# Board2.net
KiCad netlist of a schematic drawn in EAGLE
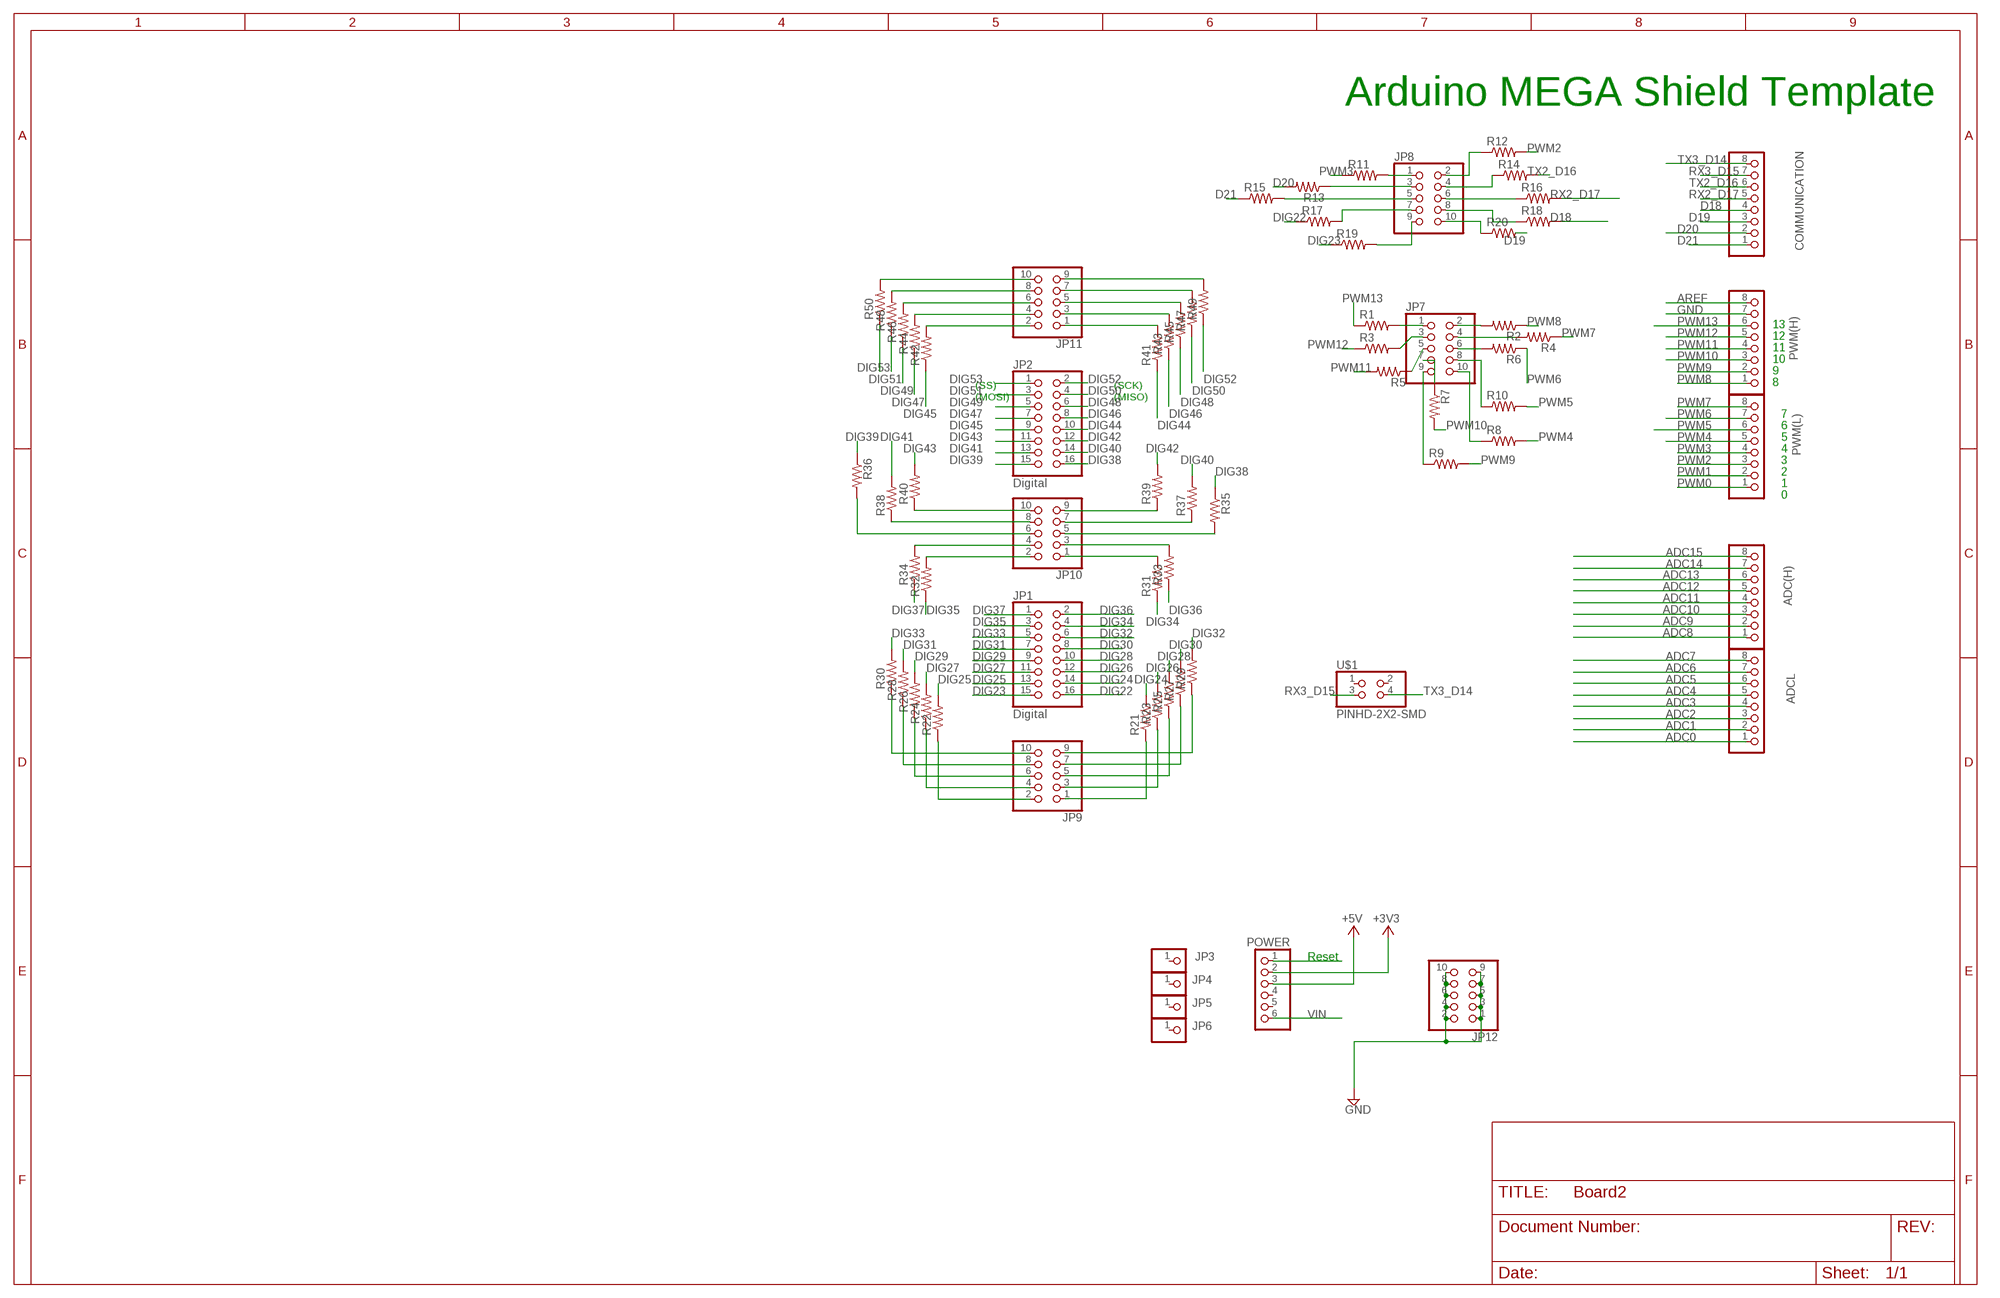
[diagram p0: schematic, sheet 1]

(export (version "E")
  (design (tool "Eeschema 10.0.6"))
  (components
    (comp (ref "ADC(H)")
      (value "PINHD-1X8")
      (footprint "eagle-import:1X08")
      (libsource (lib "eagle-import") (part "PINHD-1X8"))
    )
    (comp (ref "ADCL")
      (value "PINHD-1X8")
      (footprint "eagle-import:1X08")
      (libsource (lib "eagle-import") (part "PINHD-1X8"))
    )
    (comp (ref "COMMUNICATION")
      (value "PINHD-1X8")
      (footprint "eagle-import:1X08")
      (libsource (lib "eagle-import") (part "PINHD-1X8"))
    )
    (comp (ref "JP1")
      (value "Digital")
      (footprint "eagle-import:2X08")
      (libsource (lib "eagle-import") (part "PINHD-2X8"))
    )
    (comp (ref "JP2")
      (value "Digital")
      (footprint "eagle-import:2X08")
      (libsource (lib "eagle-import") (part "PINHD-2X8"))
    )
    (comp (ref "JP3")
      (value "PINHD-1X1")
      (footprint "eagle-import:1X01")
      (libsource (lib "eagle-import") (part "PINHD-1X1"))
    )
    (comp (ref "JP4")
      (value "PINHD-1X1")
      (footprint "eagle-import:1X01")
      (libsource (lib "eagle-import") (part "PINHD-1X1"))
    )
    (comp (ref "JP5")
      (value "PINHD-1X1")
      (footprint "eagle-import:1X01")
      (libsource (lib "eagle-import") (part "PINHD-1X1"))
    )
    (comp (ref "JP6")
      (value "PINHD-1X1")
      (footprint "eagle-import:1X01")
      (libsource (lib "eagle-import") (part "PINHD-1X1"))
    )
    (comp (ref "JP7")
      (value "PINHD-2X5SMT")
      (footprint "eagle-import:2X05_SMT")
      (libsource (lib "eagle-import") (part "PINHD-2X5SMT"))
    )
    (comp (ref "JP8")
      (value "PINHD-2X5SMT")
      (footprint "eagle-import:2X05_SMT")
      (libsource (lib "eagle-import") (part "PINHD-2X5SMT"))
    )
    (comp (ref "JP9")
      (value "PINHD-2X5SMT")
      (footprint "eagle-import:2X05_SMT")
      (libsource (lib "eagle-import") (part "PINHD-2X5SMT"))
    )
    (comp (ref "JP10")
      (value "PINHD-2X5SMT")
      (footprint "eagle-import:2X05_SMT")
      (libsource (lib "eagle-import") (part "PINHD-2X5SMT"))
    )
    (comp (ref "JP11")
      (value "PINHD-2X5SMT")
      (footprint "eagle-import:2X05_SMT")
      (libsource (lib "eagle-import") (part "PINHD-2X5SMT"))
    )
    (comp (ref "JP12")
      (value "PINHD-2X5SMT")
      (footprint "eagle-import:2X05_SMT")
      (libsource (lib "eagle-import") (part "PINHD-2X5SMT"))
    )
    (comp (ref "POWER")
      (value "PINHD-1X6")
      (footprint "eagle-import:1X06")
      (libsource (lib "eagle-import") (part "PINHD-1X6"))
    )
    (comp (ref "PWM(H)")
      (value "PINHD-1X8")
      (footprint "eagle-import:1X08")
      (libsource (lib "eagle-import") (part "PINHD-1X8"))
    )
    (comp (ref "PWM(L)")
      (value "PINHD-1X8")
      (footprint "eagle-import:1X08")
      (libsource (lib "eagle-import") (part "PINHD-1X8"))
    )
    (comp (ref "R1")
      (value "R-US_M1206")
      (footprint "eagle-import:M1206")
      (libsource (lib "eagle-import") (part "R-US_M1206"))
    )
    (comp (ref "R2")
      (value "R-US_M1206")
      (footprint "eagle-import:M1206")
      (libsource (lib "eagle-import") (part "R-US_M1206"))
    )
    (comp (ref "R3")
      (value "R-US_M1206")
      (footprint "eagle-import:M1206")
      (libsource (lib "eagle-import") (part "R-US_M1206"))
    )
    (comp (ref "R4")
      (value "R-US_M1206")
      (footprint "eagle-import:M1206")
      (libsource (lib "eagle-import") (part "R-US_M1206"))
    )
    (comp (ref "R5")
      (value "R-US_M1206")
      (footprint "eagle-import:M1206")
      (libsource (lib "eagle-import") (part "R-US_M1206"))
    )
    (comp (ref "R6")
      (value "R-US_M1206")
      (footprint "eagle-import:M1206")
      (libsource (lib "eagle-import") (part "R-US_M1206"))
    )
    (comp (ref "R7")
      (value "R-US_M1206")
      (footprint "eagle-import:M1206")
      (libsource (lib "eagle-import") (part "R-US_M1206"))
    )
    (comp (ref "R8")
      (value "R-US_M1206")
      (footprint "eagle-import:M1206")
      (libsource (lib "eagle-import") (part "R-US_M1206"))
    )
    (comp (ref "R9")
      (value "R-US_M1206")
      (footprint "eagle-import:M1206")
      (libsource (lib "eagle-import") (part "R-US_M1206"))
    )
    (comp (ref "R10")
      (value "R-US_M1206")
      (footprint "eagle-import:M1206")
      (libsource (lib "eagle-import") (part "R-US_M1206"))
    )
    (comp (ref "R11")
      (value "R-US_M1206")
      (footprint "eagle-import:M1206")
      (libsource (lib "eagle-import") (part "R-US_M1206"))
    )
    (comp (ref "R12")
      (value "R-US_M1206")
      (footprint "eagle-import:M1206")
      (libsource (lib "eagle-import") (part "R-US_M1206"))
    )
    (comp (ref "R13")
      (value "R-US_M1206")
      (footprint "eagle-import:M1206")
      (libsource (lib "eagle-import") (part "R-US_M1206"))
    )
    (comp (ref "R14")
      (value "R-US_M1206")
      (footprint "eagle-import:M1206")
      (libsource (lib "eagle-import") (part "R-US_M1206"))
    )
    (comp (ref "R15")
      (value "R-US_M1206")
      (footprint "eagle-import:M1206")
      (libsource (lib "eagle-import") (part "R-US_M1206"))
    )
    (comp (ref "R16")
      (value "R-US_M1206")
      (footprint "eagle-import:M1206")
      (libsource (lib "eagle-import") (part "R-US_M1206"))
    )
    (comp (ref "R17")
      (value "R-US_M1206")
      (footprint "eagle-import:M1206")
      (libsource (lib "eagle-import") (part "R-US_M1206"))
    )
    (comp (ref "R18")
      (value "R-US_M1206")
      (footprint "eagle-import:M1206")
      (libsource (lib "eagle-import") (part "R-US_M1206"))
    )
    (comp (ref "R19")
      (value "R-US_M1206")
      (footprint "eagle-import:M1206")
      (libsource (lib "eagle-import") (part "R-US_M1206"))
    )
    (comp (ref "R20")
      (value "R-US_M1206")
      (footprint "eagle-import:M1206")
      (libsource (lib "eagle-import") (part "R-US_M1206"))
    )
    (comp (ref "R21")
      (value "R-US_M1206")
      (footprint "eagle-import:M1206")
      (libsource (lib "eagle-import") (part "R-US_M1206"))
    )
    (comp (ref "R22")
      (value "R-US_M1206")
      (footprint "eagle-import:M1206")
      (libsource (lib "eagle-import") (part "R-US_M1206"))
    )
    (comp (ref "R23")
      (value "R-US_M1206")
      (footprint "eagle-import:M1206")
      (libsource (lib "eagle-import") (part "R-US_M1206"))
    )
    (comp (ref "R24")
      (value "R-US_M1206")
      (footprint "eagle-import:M1206")
      (libsource (lib "eagle-import") (part "R-US_M1206"))
    )
    (comp (ref "R25")
      (value "R-US_M1206")
      (footprint "eagle-import:M1206")
      (libsource (lib "eagle-import") (part "R-US_M1206"))
    )
    (comp (ref "R26")
      (value "R-US_M1206")
      (footprint "eagle-import:M1206")
      (libsource (lib "eagle-import") (part "R-US_M1206"))
    )
    (comp (ref "R27")
      (value "R-US_M1206")
      (footprint "eagle-import:M1206")
      (libsource (lib "eagle-import") (part "R-US_M1206"))
    )
    (comp (ref "R28")
      (value "R-US_M1206")
      (footprint "eagle-import:M1206")
      (libsource (lib "eagle-import") (part "R-US_M1206"))
    )
    (comp (ref "R29")
      (value "R-US_M1206")
      (footprint "eagle-import:M1206")
      (libsource (lib "eagle-import") (part "R-US_M1206"))
    )
    (comp (ref "R30")
      (value "R-US_M1206")
      (footprint "eagle-import:M1206")
      (libsource (lib "eagle-import") (part "R-US_M1206"))
    )
    (comp (ref "R31")
      (value "R-US_M1206")
      (footprint "eagle-import:M1206")
      (libsource (lib "eagle-import") (part "R-US_M1206"))
    )
    (comp (ref "R32")
      (value "R-US_M1206")
      (footprint "eagle-import:M1206")
      (libsource (lib "eagle-import") (part "R-US_M1206"))
    )
    (comp (ref "R33")
      (value "R-US_M1206")
      (footprint "eagle-import:M1206")
      (libsource (lib "eagle-import") (part "R-US_M1206"))
    )
    (comp (ref "R34")
      (value "R-US_M1206")
      (footprint "eagle-import:M1206")
      (libsource (lib "eagle-import") (part "R-US_M1206"))
    )
    (comp (ref "R35")
      (value "R-US_M1206")
      (footprint "eagle-import:M1206")
      (libsource (lib "eagle-import") (part "R-US_M1206"))
    )
    (comp (ref "R36")
      (value "R-US_M1206")
      (footprint "eagle-import:M1206")
      (libsource (lib "eagle-import") (part "R-US_M1206"))
    )
    (comp (ref "R37")
      (value "R-US_M1206")
      (footprint "eagle-import:M1206")
      (libsource (lib "eagle-import") (part "R-US_M1206"))
    )
    (comp (ref "R38")
      (value "R-US_M1206")
      (footprint "eagle-import:M1206")
      (libsource (lib "eagle-import") (part "R-US_M1206"))
    )
    (comp (ref "R39")
      (value "R-US_M1206")
      (footprint "eagle-import:M1206")
      (libsource (lib "eagle-import") (part "R-US_M1206"))
    )
    (comp (ref "R40")
      (value "R-US_M1206")
      (footprint "eagle-import:M1206")
      (libsource (lib "eagle-import") (part "R-US_M1206"))
    )
    (comp (ref "R41")
      (value "R-US_M1206")
      (footprint "eagle-import:M1206")
      (libsource (lib "eagle-import") (part "R-US_M1206"))
    )
    (comp (ref "R42")
      (value "R-US_M1206")
      (footprint "eagle-import:M1206")
      (libsource (lib "eagle-import") (part "R-US_M1206"))
    )
    (comp (ref "R43")
      (value "R-US_M1206")
      (footprint "eagle-import:M1206")
      (libsource (lib "eagle-import") (part "R-US_M1206"))
    )
    (comp (ref "R44")
      (value "R-US_M1206")
      (footprint "eagle-import:M1206")
      (libsource (lib "eagle-import") (part "R-US_M1206"))
    )
    (comp (ref "R45")
      (value "R-US_M1206")
      (footprint "eagle-import:M1206")
      (libsource (lib "eagle-import") (part "R-US_M1206"))
    )
    (comp (ref "R46")
      (value "R-US_M1206")
      (footprint "eagle-import:M1206")
      (libsource (lib "eagle-import") (part "R-US_M1206"))
    )
    (comp (ref "R47")
      (value "R-US_M1206")
      (footprint "eagle-import:M1206")
      (libsource (lib "eagle-import") (part "R-US_M1206"))
    )
    (comp (ref "R48")
      (value "R-US_M1206")
      (footprint "eagle-import:M1206")
      (libsource (lib "eagle-import") (part "R-US_M1206"))
    )
    (comp (ref "R49")
      (value "R-US_M1206")
      (footprint "eagle-import:M1206")
      (libsource (lib "eagle-import") (part "R-US_M1206"))
    )
    (comp (ref "R50")
      (value "R-US_M1206")
      (footprint "eagle-import:M1206")
      (libsource (lib "eagle-import") (part "R-US_M1206"))
    )
    (comp (ref "U$1")
      (value "PINHD-2X2-SMD")
      (footprint "eagle-import:2X02SMD")
      (libsource (lib "eagle-import") (part "PINHD-2X2-SMD"))
    )
  )
  (nets
    (net (code "1") (name "+3V3") (class "Default")
      (node (ref "POWER") (pin "2") (pinfunction "2_2") (pintype "passive"))
    )
    (net (code "2") (name "+5V") (class "Default")
      (node (ref "POWER") (pin "3") (pinfunction "3_3") (pintype "passive"))
    )
    (net (code "3") (name "/ADC0") (class "Default")
      (node (ref "ADCL") (pin "1") (pinfunction "1_1") (pintype "passive"))
    )
    (net (code "4") (name "/ADC1") (class "Default")
      (node (ref "ADCL") (pin "2") (pinfunction "2_2") (pintype "passive"))
    )
    (net (code "5") (name "/ADC2") (class "Default")
      (node (ref "ADCL") (pin "3") (pinfunction "3_3") (pintype "passive"))
    )
    (net (code "6") (name "/ADC3") (class "Default")
      (node (ref "ADCL") (pin "4") (pinfunction "4_4") (pintype "passive"))
    )
    (net (code "7") (name "/ADC4") (class "Default")
      (node (ref "ADCL") (pin "5") (pinfunction "5_5") (pintype "passive"))
    )
    (net (code "8") (name "/ADC5") (class "Default")
      (node (ref "ADCL") (pin "6") (pinfunction "6_6") (pintype "passive"))
    )
    (net (code "9") (name "/ADC6") (class "Default")
      (node (ref "ADCL") (pin "7") (pinfunction "7_7") (pintype "passive"))
    )
    (net (code "10") (name "/ADC7") (class "Default")
      (node (ref "ADCL") (pin "8") (pinfunction "8_8") (pintype "passive"))
    )
    (net (code "11") (name "/ADC8") (class "Default")
      (node (ref "ADC(H)") (pin "1") (pinfunction "1_1") (pintype "passive"))
    )
    (net (code "12") (name "/ADC9") (class "Default")
      (node (ref "ADC(H)") (pin "2") (pinfunction "2_2") (pintype "passive"))
    )
    (net (code "13") (name "/ADC10") (class "Default")
      (node (ref "ADC(H)") (pin "3") (pinfunction "3_3") (pintype "passive"))
    )
    (net (code "14") (name "/ADC11") (class "Default")
      (node (ref "ADC(H)") (pin "4") (pinfunction "4_4") (pintype "passive"))
    )
    (net (code "15") (name "/ADC12") (class "Default")
      (node (ref "ADC(H)") (pin "5") (pinfunction "5_5") (pintype "passive"))
    )
    (net (code "16") (name "/ADC13") (class "Default")
      (node (ref "ADC(H)") (pin "6") (pinfunction "6_6") (pintype "passive"))
    )
    (net (code "17") (name "/ADC14") (class "Default")
      (node (ref "ADC(H)") (pin "7") (pinfunction "7_7") (pintype "passive"))
    )
    (net (code "18") (name "/ADC15") (class "Default")
      (node (ref "ADC(H)") (pin "8") (pinfunction "8_8") (pintype "passive"))
    )
    (net (code "19") (name "/AREF") (class "Default")
      (node (ref "PWM(H)") (pin "8") (pinfunction "8_8") (pintype "passive"))
    )
    (net (code "20") (name "/D18") (class "Default")
      (node (ref "COMMUNICATION") (pin "4") (pinfunction "4_4") (pintype "passive"))
      (node (ref "R18") (pin "2") (pinfunction "2_2") (pintype "passive"))
    )
    (net (code "21") (name "/D19") (class "Default")
      (node (ref "COMMUNICATION") (pin "3") (pinfunction "3_3") (pintype "passive"))
      (node (ref "R20") (pin "2") (pinfunction "2_2") (pintype "passive"))
    )
    (net (code "22") (name "/D20") (class "Default")
      (node (ref "COMMUNICATION") (pin "2") (pinfunction "2_2") (pintype "passive"))
      (node (ref "R13") (pin "2") (pinfunction "2_2") (pintype "passive"))
    )
    (net (code "23") (name "/D21") (class "Default")
      (node (ref "COMMUNICATION") (pin "1") (pinfunction "1_1") (pintype "passive"))
      (node (ref "R15") (pin "1") (pinfunction "1_1") (pintype "passive"))
    )
    (net (code "24") (name "/DIG22") (class "Default")
      (node (ref "JP1") (pin "16") (pinfunction "16_16") (pintype "passive"))
      (node (ref "R17") (pin "1") (pinfunction "1_1") (pintype "passive"))
    )
    (net (code "25") (name "/DIG23") (class "Default")
      (node (ref "JP1") (pin "15") (pinfunction "15_15") (pintype "passive"))
      (node (ref "R19") (pin "1") (pinfunction "1_1") (pintype "passive"))
    )
    (net (code "26") (name "/DIG24") (class "Default")
      (node (ref "JP1") (pin "14") (pinfunction "14_14") (pintype "passive"))
      (node (ref "R21") (pin "2") (pinfunction "2_2") (pintype "passive"))
    )
    (net (code "27") (name "/DIG25") (class "Default")
      (node (ref "JP1") (pin "13") (pinfunction "13_13") (pintype "passive"))
      (node (ref "R22") (pin "2") (pinfunction "2_2") (pintype "passive"))
    )
    (net (code "28") (name "/DIG26") (class "Default")
      (node (ref "JP1") (pin "12") (pinfunction "12_12") (pintype "passive"))
      (node (ref "R23") (pin "2") (pinfunction "2_2") (pintype "passive"))
    )
    (net (code "29") (name "/DIG27") (class "Default")
      (node (ref "JP1") (pin "11") (pinfunction "11_11") (pintype "passive"))
      (node (ref "R24") (pin "2") (pinfunction "2_2") (pintype "passive"))
    )
    (net (code "30") (name "/DIG28") (class "Default")
      (node (ref "JP1") (pin "10") (pinfunction "10_10") (pintype "passive"))
      (node (ref "R25") (pin "2") (pinfunction "2_2") (pintype "passive"))
    )
    (net (code "31") (name "/DIG29") (class "Default")
      (node (ref "JP1") (pin "9") (pinfunction "9_9") (pintype "passive"))
      (node (ref "R26") (pin "2") (pinfunction "2_2") (pintype "passive"))
    )
    (net (code "32") (name "/DIG30") (class "Default")
      (node (ref "JP1") (pin "8") (pinfunction "8_8") (pintype "passive"))
      (node (ref "R27") (pin "2") (pinfunction "2_2") (pintype "passive"))
    )
    (net (code "33") (name "/DIG31") (class "Default")
      (node (ref "JP1") (pin "7") (pinfunction "7_7") (pintype "passive"))
      (node (ref "R28") (pin "2") (pinfunction "2_2") (pintype "passive"))
    )
    (net (code "34") (name "/DIG32") (class "Default")
      (node (ref "JP1") (pin "6") (pinfunction "6_6") (pintype "passive"))
      (node (ref "R29") (pin "2") (pinfunction "2_2") (pintype "passive"))
    )
    (net (code "35") (name "/DIG33") (class "Default")
      (node (ref "JP1") (pin "5") (pinfunction "5_5") (pintype "passive"))
      (node (ref "R30") (pin "2") (pinfunction "2_2") (pintype "passive"))
    )
    (net (code "36") (name "/DIG34") (class "Default")
      (node (ref "JP1") (pin "4") (pinfunction "4_4") (pintype "passive"))
      (node (ref "R31") (pin "1") (pinfunction "1_1") (pintype "passive"))
    )
    (net (code "37") (name "/DIG35") (class "Default")
      (node (ref "JP1") (pin "3") (pinfunction "3_3") (pintype "passive"))
      (node (ref "R32") (pin "1") (pinfunction "1_1") (pintype "passive"))
    )
    (net (code "38") (name "/DIG36") (class "Default")
      (node (ref "JP1") (pin "2") (pinfunction "2_2") (pintype "passive"))
      (node (ref "R33") (pin "1") (pinfunction "1_1") (pintype "passive"))
    )
    (net (code "39") (name "/DIG37") (class "Default")
      (node (ref "JP1") (pin "1") (pinfunction "1_1") (pintype "passive"))
      (node (ref "R34") (pin "1") (pinfunction "1_1") (pintype "passive"))
    )
    (net (code "40") (name "/DIG38") (class "Default")
      (node (ref "JP2") (pin "16") (pinfunction "16_16") (pintype "passive"))
      (node (ref "R35") (pin "1") (pinfunction "1_1") (pintype "passive"))
    )
    (net (code "41") (name "/DIG39") (class "Default")
      (node (ref "JP2") (pin "15") (pinfunction "15_15") (pintype "passive"))
      (node (ref "R36") (pin "1") (pinfunction "1_1") (pintype "passive"))
    )
    (net (code "42") (name "/DIG40") (class "Default")
      (node (ref "JP2") (pin "14") (pinfunction "14_14") (pintype "passive"))
      (node (ref "R37") (pin "2") (pinfunction "2_2") (pintype "passive"))
    )
    (net (code "43") (name "/DIG41") (class "Default")
      (node (ref "JP2") (pin "13") (pinfunction "13_13") (pintype "passive"))
      (node (ref "R38") (pin "2") (pinfunction "2_2") (pintype "passive"))
    )
    (net (code "44") (name "/DIG42") (class "Default")
      (node (ref "JP2") (pin "12") (pinfunction "12_12") (pintype "passive"))
      (node (ref "R39") (pin "2") (pinfunction "2_2") (pintype "passive"))
    )
    (net (code "45") (name "/DIG43") (class "Default")
      (node (ref "JP2") (pin "11") (pinfunction "11_11") (pintype "passive"))
      (node (ref "R40") (pin "2") (pinfunction "2_2") (pintype "passive"))
    )
    (net (code "46") (name "/DIG44") (class "Default")
      (node (ref "JP2") (pin "10") (pinfunction "10_10") (pintype "passive"))
      (node (ref "R41") (pin "1") (pinfunction "1_1") (pintype "passive"))
    )
    (net (code "47") (name "/DIG45") (class "Default")
      (node (ref "JP2") (pin "9") (pinfunction "9_9") (pintype "passive"))
      (node (ref "R42") (pin "1") (pinfunction "1_1") (pintype "passive"))
    )
    (net (code "48") (name "/DIG46") (class "Default")
      (node (ref "JP2") (pin "8") (pinfunction "8_8") (pintype "passive"))
      (node (ref "R43") (pin "1") (pinfunction "1_1") (pintype "passive"))
    )
    (net (code "49") (name "/DIG47") (class "Default")
      (node (ref "JP2") (pin "7") (pinfunction "7_7") (pintype "passive"))
      (node (ref "R44") (pin "1") (pinfunction "1_1") (pintype "passive"))
    )
    (net (code "50") (name "/DIG48") (class "Default")
      (node (ref "JP2") (pin "6") (pinfunction "6_6") (pintype "passive"))
      (node (ref "R45") (pin "1") (pinfunction "1_1") (pintype "passive"))
    )
    (net (code "51") (name "/DIG49") (class "Default")
      (node (ref "JP2") (pin "5") (pinfunction "5_5") (pintype "passive"))
      (node (ref "R46") (pin "1") (pinfunction "1_1") (pintype "passive"))
    )
    (net (code "52") (name "/DIG50") (class "Default")
      (node (ref "JP2") (pin "4") (pinfunction "4_4") (pintype "passive"))
      (node (ref "R47") (pin "1") (pinfunction "1_1") (pintype "passive"))
    )
    (net (code "53") (name "/DIG51") (class "Default")
      (node (ref "JP2") (pin "3") (pinfunction "3_3") (pintype "passive"))
      (node (ref "R48") (pin "1") (pinfunction "1_1") (pintype "passive"))
    )
    (net (code "54") (name "/DIG52") (class "Default")
      (node (ref "JP2") (pin "2") (pinfunction "2_2") (pintype "passive"))
      (node (ref "R49") (pin "1") (pinfunction "1_1") (pintype "passive"))
    )
    (net (code "55") (name "/DIG53") (class "Default")
      (node (ref "JP2") (pin "1") (pinfunction "1_1") (pintype "passive"))
      (node (ref "R50") (pin "1") (pinfunction "1_1") (pintype "passive"))
    )
    (net (code "56") (name "/PWM0") (class "Default")
      (node (ref "PWM(L)") (pin "1") (pinfunction "1_1") (pintype "passive"))
    )
    (net (code "57") (name "/PWM1") (class "Default")
      (node (ref "PWM(L)") (pin "2") (pinfunction "2_2") (pintype "passive"))
    )
    (net (code "58") (name "/PWM2") (class "Default")
      (node (ref "PWM(L)") (pin "3") (pinfunction "3_3") (pintype "passive"))
      (node (ref "R12") (pin "2") (pinfunction "2_2") (pintype "passive"))
    )
    (net (code "59") (name "/PWM3") (class "Default")
      (node (ref "PWM(L)") (pin "4") (pinfunction "4_4") (pintype "passive"))
      (node (ref "R11") (pin "1") (pinfunction "1_1") (pintype "passive"))
    )
    (net (code "60") (name "/PWM4") (class "Default")
      (node (ref "PWM(L)") (pin "5") (pinfunction "5_5") (pintype "passive"))
      (node (ref "R8") (pin "2") (pinfunction "2_2") (pintype "passive"))
    )
    (net (code "61") (name "/PWM5") (class "Default")
      (node (ref "PWM(L)") (pin "6") (pinfunction "6_6") (pintype "passive"))
      (node (ref "R10") (pin "2") (pinfunction "2_2") (pintype "passive"))
    )
    (net (code "62") (name "/PWM6") (class "Default")
      (node (ref "PWM(L)") (pin "7") (pinfunction "7_7") (pintype "passive"))
      (node (ref "R6") (pin "1") (pinfunction "1_1") (pintype "passive"))
    )
    (net (code "63") (name "/PWM7") (class "Default")
      (node (ref "PWM(L)") (pin "8") (pinfunction "8_8") (pintype "passive"))
      (node (ref "R4") (pin "1") (pinfunction "1_1") (pintype "passive"))
    )
    (net (code "64") (name "/PWM8") (class "Default")
      (node (ref "PWM(H)") (pin "1") (pinfunction "1_1") (pintype "passive"))
      (node (ref "R2") (pin "1") (pinfunction "1_1") (pintype "passive"))
    )
    (net (code "65") (name "/PWM9") (class "Default")
      (node (ref "PWM(H)") (pin "2") (pinfunction "2_2") (pintype "passive"))
      (node (ref "R9") (pin "2") (pinfunction "2_2") (pintype "passive"))
    )
    (net (code "66") (name "/PWM10") (class "Default")
      (node (ref "PWM(H)") (pin "3") (pinfunction "3_3") (pintype "passive"))
      (node (ref "R7") (pin "2") (pinfunction "2_2") (pintype "passive"))
    )
    (net (code "67") (name "/PWM11") (class "Default")
      (node (ref "PWM(H)") (pin "4") (pinfunction "4_4") (pintype "passive"))
      (node (ref "R5") (pin "2") (pinfunction "2_2") (pintype "passive"))
    )
    (net (code "68") (name "/PWM12") (class "Default")
      (node (ref "PWM(H)") (pin "5") (pinfunction "5_5") (pintype "passive"))
      (node (ref "R3") (pin "1") (pinfunction "1_1") (pintype "passive"))
    )
    (net (code "69") (name "/PWM13") (class "Default")
      (node (ref "PWM(H)") (pin "6") (pinfunction "6_6") (pintype "passive"))
      (node (ref "R1") (pin "1") (pinfunction "1_1") (pintype "passive"))
    )
    (net (code "70") (name "/RX2_D17") (class "Default")
      (node (ref "COMMUNICATION") (pin "5") (pinfunction "5_5") (pintype "passive"))
      (node (ref "R16") (pin "2") (pinfunction "2_2") (pintype "passive"))
    )
    (net (code "71") (name "/RX3_D15") (class "Default")
      (node (ref "COMMUNICATION") (pin "7") (pinfunction "7_7") (pintype "passive"))
      (node (ref "U$1") (pin "3") (pinfunction "3_3") (pintype "passive"))
    )
    (net (code "72") (name "/TX2_D16") (class "Default")
      (node (ref "COMMUNICATION") (pin "6") (pinfunction "6_6") (pintype "passive"))
      (node (ref "R14") (pin "2") (pinfunction "2_2") (pintype "passive"))
    )
    (net (code "73") (name "/TX3_D14") (class "Default")
      (node (ref "COMMUNICATION") (pin "8") (pinfunction "8_8") (pintype "passive"))
      (node (ref "U$1") (pin "4") (pinfunction "4_4") (pintype "passive"))
    )
    (net (code "74") (name "/VIN") (class "Default")
      (node (ref "POWER") (pin "6") (pinfunction "6_6") (pintype "passive"))
    )
    (net (code "75") (name "GND") (class "Default")
      (node (ref "JP12") (pin "1") (pinfunction "1_1") (pintype "passive"))
      (node (ref "JP12") (pin "10") (pinfunction "10_10") (pintype "passive"))
      (node (ref "JP12") (pin "2") (pinfunction "2_2") (pintype "passive"))
      (node (ref "JP12") (pin "3") (pinfunction "3_3") (pintype "passive"))
      (node (ref "JP12") (pin "4") (pinfunction "4_4") (pintype "passive"))
      (node (ref "JP12") (pin "5") (pinfunction "5_5") (pintype "passive"))
      (node (ref "JP12") (pin "6") (pinfunction "6_6") (pintype "passive"))
      (node (ref "JP12") (pin "7") (pinfunction "7_7") (pintype "passive"))
      (node (ref "JP12") (pin "8") (pinfunction "8_8") (pintype "passive"))
      (node (ref "JP12") (pin "9") (pinfunction "9_9") (pintype "passive"))
      (node (ref "PWM(H)") (pin "7") (pinfunction "7_7") (pintype "passive"))
    )
    (net (code "76") (name "Net-(JP7-Pad1)") (class "Default")
      (node (ref "JP7") (pin "1") (pinfunction "1_1") (pintype "passive"))
      (node (ref "R1") (pin "2") (pinfunction "2_2") (pintype "passive"))
    )
    (net (code "77") (name "Net-(JP7-Pad2)") (class "Default")
      (node (ref "JP7") (pin "2") (pinfunction "2_2") (pintype "passive"))
      (node (ref "R2") (pin "2") (pinfunction "2_2") (pintype "passive"))
    )
    (net (code "78") (name "Net-(JP7-Pad3)") (class "Default")
      (node (ref "JP7") (pin "3") (pinfunction "3_3") (pintype "passive"))
      (node (ref "R3") (pin "2") (pinfunction "2_2") (pintype "passive"))
    )
    (net (code "79") (name "Net-(JP7-Pad4)") (class "Default")
      (node (ref "JP7") (pin "4") (pinfunction "4_4") (pintype "passive"))
      (node (ref "R4") (pin "2") (pinfunction "2_2") (pintype "passive"))
    )
    (net (code "80") (name "Net-(JP7-Pad5)") (class "Default")
      (node (ref "JP7") (pin "5") (pinfunction "5_5") (pintype "passive"))
      (node (ref "R5") (pin "1") (pinfunction "1_1") (pintype "passive"))
    )
    (net (code "81") (name "Net-(JP7-Pad6)") (class "Default")
      (node (ref "JP7") (pin "6") (pinfunction "6_6") (pintype "passive"))
      (node (ref "R6") (pin "2") (pinfunction "2_2") (pintype "passive"))
    )
    (net (code "82") (name "Net-(JP7-Pad7)") (class "Default")
      (node (ref "JP7") (pin "7") (pinfunction "7_7") (pintype "passive"))
      (node (ref "R7") (pin "1") (pinfunction "1_1") (pintype "passive"))
    )
    (net (code "83") (name "Net-(JP7-Pad8)") (class "Default")
      (node (ref "JP7") (pin "8") (pinfunction "8_8") (pintype "passive"))
      (node (ref "R10") (pin "1") (pinfunction "1_1") (pintype "passive"))
    )
    (net (code "84") (name "Net-(JP7-Pad9)") (class "Default")
      (node (ref "JP7") (pin "9") (pinfunction "9_9") (pintype "passive"))
      (node (ref "R9") (pin "1") (pinfunction "1_1") (pintype "passive"))
    )
    (net (code "85") (name "Net-(JP7-Pad10)") (class "Default")
      (node (ref "JP7") (pin "10") (pinfunction "10_10") (pintype "passive"))
      (node (ref "R8") (pin "1") (pinfunction "1_1") (pintype "passive"))
    )
    (net (code "86") (name "Net-(JP8-Pad1)") (class "Default")
      (node (ref "JP8") (pin "1") (pinfunction "1_1") (pintype "passive"))
      (node (ref "R11") (pin "2") (pinfunction "2_2") (pintype "passive"))
    )
    (net (code "87") (name "Net-(JP8-Pad2)") (class "Default")
      (node (ref "JP8") (pin "2") (pinfunction "2_2") (pintype "passive"))
      (node (ref "R12") (pin "1") (pinfunction "1_1") (pintype "passive"))
    )
    (net (code "88") (name "Net-(JP8-Pad3)") (class "Default")
      (node (ref "JP8") (pin "3") (pinfunction "3_3") (pintype "passive"))
      (node (ref "R13") (pin "1") (pinfunction "1_1") (pintype "passive"))
    )
    (net (code "89") (name "Net-(JP8-Pad4)") (class "Default")
      (node (ref "JP8") (pin "4") (pinfunction "4_4") (pintype "passive"))
      (node (ref "R14") (pin "1") (pinfunction "1_1") (pintype "passive"))
    )
    (net (code "90") (name "Net-(JP8-Pad5)") (class "Default")
      (node (ref "JP8") (pin "5") (pinfunction "5_5") (pintype "passive"))
      (node (ref "R15") (pin "2") (pinfunction "2_2") (pintype "passive"))
    )
    (net (code "91") (name "Net-(JP8-Pad6)") (class "Default")
      (node (ref "JP8") (pin "6") (pinfunction "6_6") (pintype "passive"))
      (node (ref "R16") (pin "1") (pinfunction "1_1") (pintype "passive"))
    )
    (net (code "92") (name "Net-(JP8-Pad7)") (class "Default")
      (node (ref "JP8") (pin "7") (pinfunction "7_7") (pintype "passive"))
      (node (ref "R17") (pin "2") (pinfunction "2_2") (pintype "passive"))
    )
    (net (code "93") (name "Net-(JP8-Pad8)") (class "Default")
      (node (ref "JP8") (pin "8") (pinfunction "8_8") (pintype "passive"))
      (node (ref "R18") (pin "1") (pinfunction "1_1") (pintype "passive"))
    )
    (net (code "94") (name "Net-(JP8-Pad9)") (class "Default")
      (node (ref "JP8") (pin "9") (pinfunction "9_9") (pintype "passive"))
      (node (ref "R19") (pin "2") (pinfunction "2_2") (pintype "passive"))
    )
    (net (code "95") (name "Net-(JP8-Pad10)") (class "Default")
      (node (ref "JP8") (pin "10") (pinfunction "10_10") (pintype "passive"))
      (node (ref "R20") (pin "1") (pinfunction "1_1") (pintype "passive"))
    )
    (net (code "96") (name "Net-(JP9-Pad1)") (class "Default")
      (node (ref "JP9") (pin "1") (pinfunction "1_1") (pintype "passive"))
      (node (ref "R21") (pin "1") (pinfunction "1_1") (pintype "passive"))
    )
    (net (code "97") (name "Net-(JP9-Pad2)") (class "Default")
      (node (ref "JP9") (pin "2") (pinfunction "2_2") (pintype "passive"))
      (node (ref "R22") (pin "1") (pinfunction "1_1") (pintype "passive"))
    )
    (net (code "98") (name "Net-(JP9-Pad3)") (class "Default")
      (node (ref "JP9") (pin "3") (pinfunction "3_3") (pintype "passive"))
      (node (ref "R23") (pin "1") (pinfunction "1_1") (pintype "passive"))
    )
    (net (code "99") (name "Net-(JP9-Pad4)") (class "Default")
      (node (ref "JP9") (pin "4") (pinfunction "4_4") (pintype "passive"))
      (node (ref "R24") (pin "1") (pinfunction "1_1") (pintype "passive"))
    )
    (net (code "100") (name "Net-(JP9-Pad5)") (class "Default")
      (node (ref "JP9") (pin "5") (pinfunction "5_5") (pintype "passive"))
      (node (ref "R25") (pin "1") (pinfunction "1_1") (pintype "passive"))
    )
    (net (code "101") (name "Net-(JP9-Pad6)") (class "Default")
      (node (ref "JP9") (pin "6") (pinfunction "6_6") (pintype "passive"))
      (node (ref "R26") (pin "1") (pinfunction "1_1") (pintype "passive"))
    )
    (net (code "102") (name "Net-(JP9-Pad7)") (class "Default")
      (node (ref "JP9") (pin "7") (pinfunction "7_7") (pintype "passive"))
      (node (ref "R27") (pin "1") (pinfunction "1_1") (pintype "passive"))
    )
    (net (code "103") (name "Net-(JP9-Pad8)") (class "Default")
      (node (ref "JP9") (pin "8") (pinfunction "8_8") (pintype "passive"))
      (node (ref "R28") (pin "1") (pinfunction "1_1") (pintype "passive"))
    )
    (net (code "104") (name "Net-(JP9-Pad9)") (class "Default")
      (node (ref "JP9") (pin "9") (pinfunction "9_9") (pintype "passive"))
      (node (ref "R29") (pin "1") (pinfunction "1_1") (pintype "passive"))
    )
    (net (code "105") (name "Net-(JP9-Pad10)") (class "Default")
      (node (ref "JP9") (pin "10") (pinfunction "10_10") (pintype "passive"))
      (node (ref "R30") (pin "1") (pinfunction "1_1") (pintype "passive"))
    )
    (net (code "106") (name "Net-(JP10-Pad1)") (class "Default")
      (node (ref "JP10") (pin "1") (pinfunction "1_1") (pintype "passive"))
      (node (ref "R31") (pin "2") (pinfunction "2_2") (pintype "passive"))
    )
    (net (code "107") (name "Net-(JP10-Pad2)") (class "Default")
      (node (ref "JP10") (pin "2") (pinfunction "2_2") (pintype "passive"))
      (node (ref "R32") (pin "2") (pinfunction "2_2") (pintype "passive"))
    )
    (net (code "108") (name "Net-(JP10-Pad3)") (class "Default")
      (node (ref "JP10") (pin "3") (pinfunction "3_3") (pintype "passive"))
      (node (ref "R33") (pin "2") (pinfunction "2_2") (pintype "passive"))
    )
    (net (code "109") (name "Net-(JP10-Pad4)") (class "Default")
      (node (ref "JP10") (pin "4") (pinfunction "4_4") (pintype "passive"))
      (node (ref "R34") (pin "2") (pinfunction "2_2") (pintype "passive"))
    )
    (net (code "110") (name "Net-(JP10-Pad5)") (class "Default")
      (node (ref "JP10") (pin "5") (pinfunction "5_5") (pintype "passive"))
      (node (ref "R35") (pin "2") (pinfunction "2_2") (pintype "passive"))
    )
    (net (code "111") (name "Net-(JP10-Pad6)") (class "Default")
      (node (ref "JP10") (pin "6") (pinfunction "6_6") (pintype "passive"))
      (node (ref "R36") (pin "2") (pinfunction "2_2") (pintype "passive"))
    )
    (net (code "112") (name "Net-(JP10-Pad7)") (class "Default")
      (node (ref "JP10") (pin "7") (pinfunction "7_7") (pintype "passive"))
      (node (ref "R37") (pin "1") (pinfunction "1_1") (pintype "passive"))
    )
    (net (code "113") (name "Net-(JP10-Pad8)") (class "Default")
      (node (ref "JP10") (pin "8") (pinfunction "8_8") (pintype "passive"))
      (node (ref "R38") (pin "1") (pinfunction "1_1") (pintype "passive"))
    )
    (net (code "114") (name "Net-(JP10-Pad9)") (class "Default")
      (node (ref "JP10") (pin "9") (pinfunction "9_9") (pintype "passive"))
      (node (ref "R39") (pin "1") (pinfunction "1_1") (pintype "passive"))
    )
    (net (code "115") (name "Net-(JP10-Pad10)") (class "Default")
      (node (ref "JP10") (pin "10") (pinfunction "10_10") (pintype "passive"))
      (node (ref "R40") (pin "1") (pinfunction "1_1") (pintype "passive"))
    )
    (net (code "116") (name "Net-(JP11-Pad1)") (class "Default")
      (node (ref "JP11") (pin "1") (pinfunction "1_1") (pintype "passive"))
      (node (ref "R41") (pin "2") (pinfunction "2_2") (pintype "passive"))
    )
    (net (code "117") (name "Net-(JP11-Pad2)") (class "Default")
      (node (ref "JP11") (pin "2") (pinfunction "2_2") (pintype "passive"))
      (node (ref "R42") (pin "2") (pinfunction "2_2") (pintype "passive"))
    )
    (net (code "118") (name "Net-(JP11-Pad3)") (class "Default")
      (node (ref "JP11") (pin "3") (pinfunction "3_3") (pintype "passive"))
      (node (ref "R43") (pin "2") (pinfunction "2_2") (pintype "passive"))
    )
    (net (code "119") (name "Net-(JP11-Pad4)") (class "Default")
      (node (ref "JP11") (pin "4") (pinfunction "4_4") (pintype "passive"))
      (node (ref "R44") (pin "2") (pinfunction "2_2") (pintype "passive"))
    )
    (net (code "120") (name "Net-(JP11-Pad5)") (class "Default")
      (node (ref "JP11") (pin "5") (pinfunction "5_5") (pintype "passive"))
      (node (ref "R45") (pin "2") (pinfunction "2_2") (pintype "passive"))
    )
    (net (code "121") (name "Net-(JP11-Pad6)") (class "Default")
      (node (ref "JP11") (pin "6") (pinfunction "6_6") (pintype "passive"))
      (node (ref "R46") (pin "2") (pinfunction "2_2") (pintype "passive"))
    )
    (net (code "122") (name "Net-(JP11-Pad7)") (class "Default")
      (node (ref "JP11") (pin "7") (pinfunction "7_7") (pintype "passive"))
      (node (ref "R47") (pin "2") (pinfunction "2_2") (pintype "passive"))
    )
    (net (code "123") (name "Net-(JP11-Pad8)") (class "Default")
      (node (ref "JP11") (pin "8") (pinfunction "8_8") (pintype "passive"))
      (node (ref "R48") (pin "2") (pinfunction "2_2") (pintype "passive"))
    )
    (net (code "124") (name "Net-(JP11-Pad9)") (class "Default")
      (node (ref "JP11") (pin "9") (pinfunction "9_9") (pintype "passive"))
      (node (ref "R49") (pin "2") (pinfunction "2_2") (pintype "passive"))
    )
    (net (code "125") (name "Net-(JP11-Pad10)") (class "Default")
      (node (ref "JP11") (pin "10") (pinfunction "10_10") (pintype "passive"))
      (node (ref "R50") (pin "2") (pinfunction "2_2") (pintype "passive"))
    )
    (net (code "126") (name "unconnected-(JP3-Pad1)") (class "Default")
      (node (ref "JP3") (pin "1") (pinfunction "1_1") (pintype "passive"))
    )
    (net (code "127") (name "unconnected-(JP4-Pad1)") (class "Default")
      (node (ref "JP4") (pin "1") (pinfunction "1_1") (pintype "passive"))
    )
    (net (code "128") (name "unconnected-(JP5-Pad1)") (class "Default")
      (node (ref "JP5") (pin "1") (pinfunction "1_1") (pintype "passive"))
    )
    (net (code "129") (name "unconnected-(JP6-Pad1)") (class "Default")
      (node (ref "JP6") (pin "1") (pinfunction "1_1") (pintype "passive"))
    )
    (net (code "130") (name "unconnected-(POWER-Pad1)") (class "Default")
      (node (ref "POWER") (pin "1") (pinfunction "1_1") (pintype "passive"))
    )
    (net (code "131") (name "unconnected-(POWER-Pad4)") (class "Default")
      (node (ref "POWER") (pin "4") (pinfunction "4_4") (pintype "passive"))
    )
    (net (code "132") (name "unconnected-(POWER-Pad5)") (class "Default")
      (node (ref "POWER") (pin "5") (pinfunction "5_5") (pintype "passive"))
    )
    (net (code "133") (name "unconnected-(U$1-Pad1)") (class "Default")
      (node (ref "U$1") (pin "1") (pinfunction "1_1") (pintype "passive"))
    )
    (net (code "134") (name "unconnected-(U$1-Pad2)") (class "Default")
      (node (ref "U$1") (pin "2") (pinfunction "2_2") (pintype "passive"))
    )
  )
)
